# snc98_Display_15x7-Seg_3-digit_LTD040.net
KiCad netlist of a schematic drawn in EAGLE
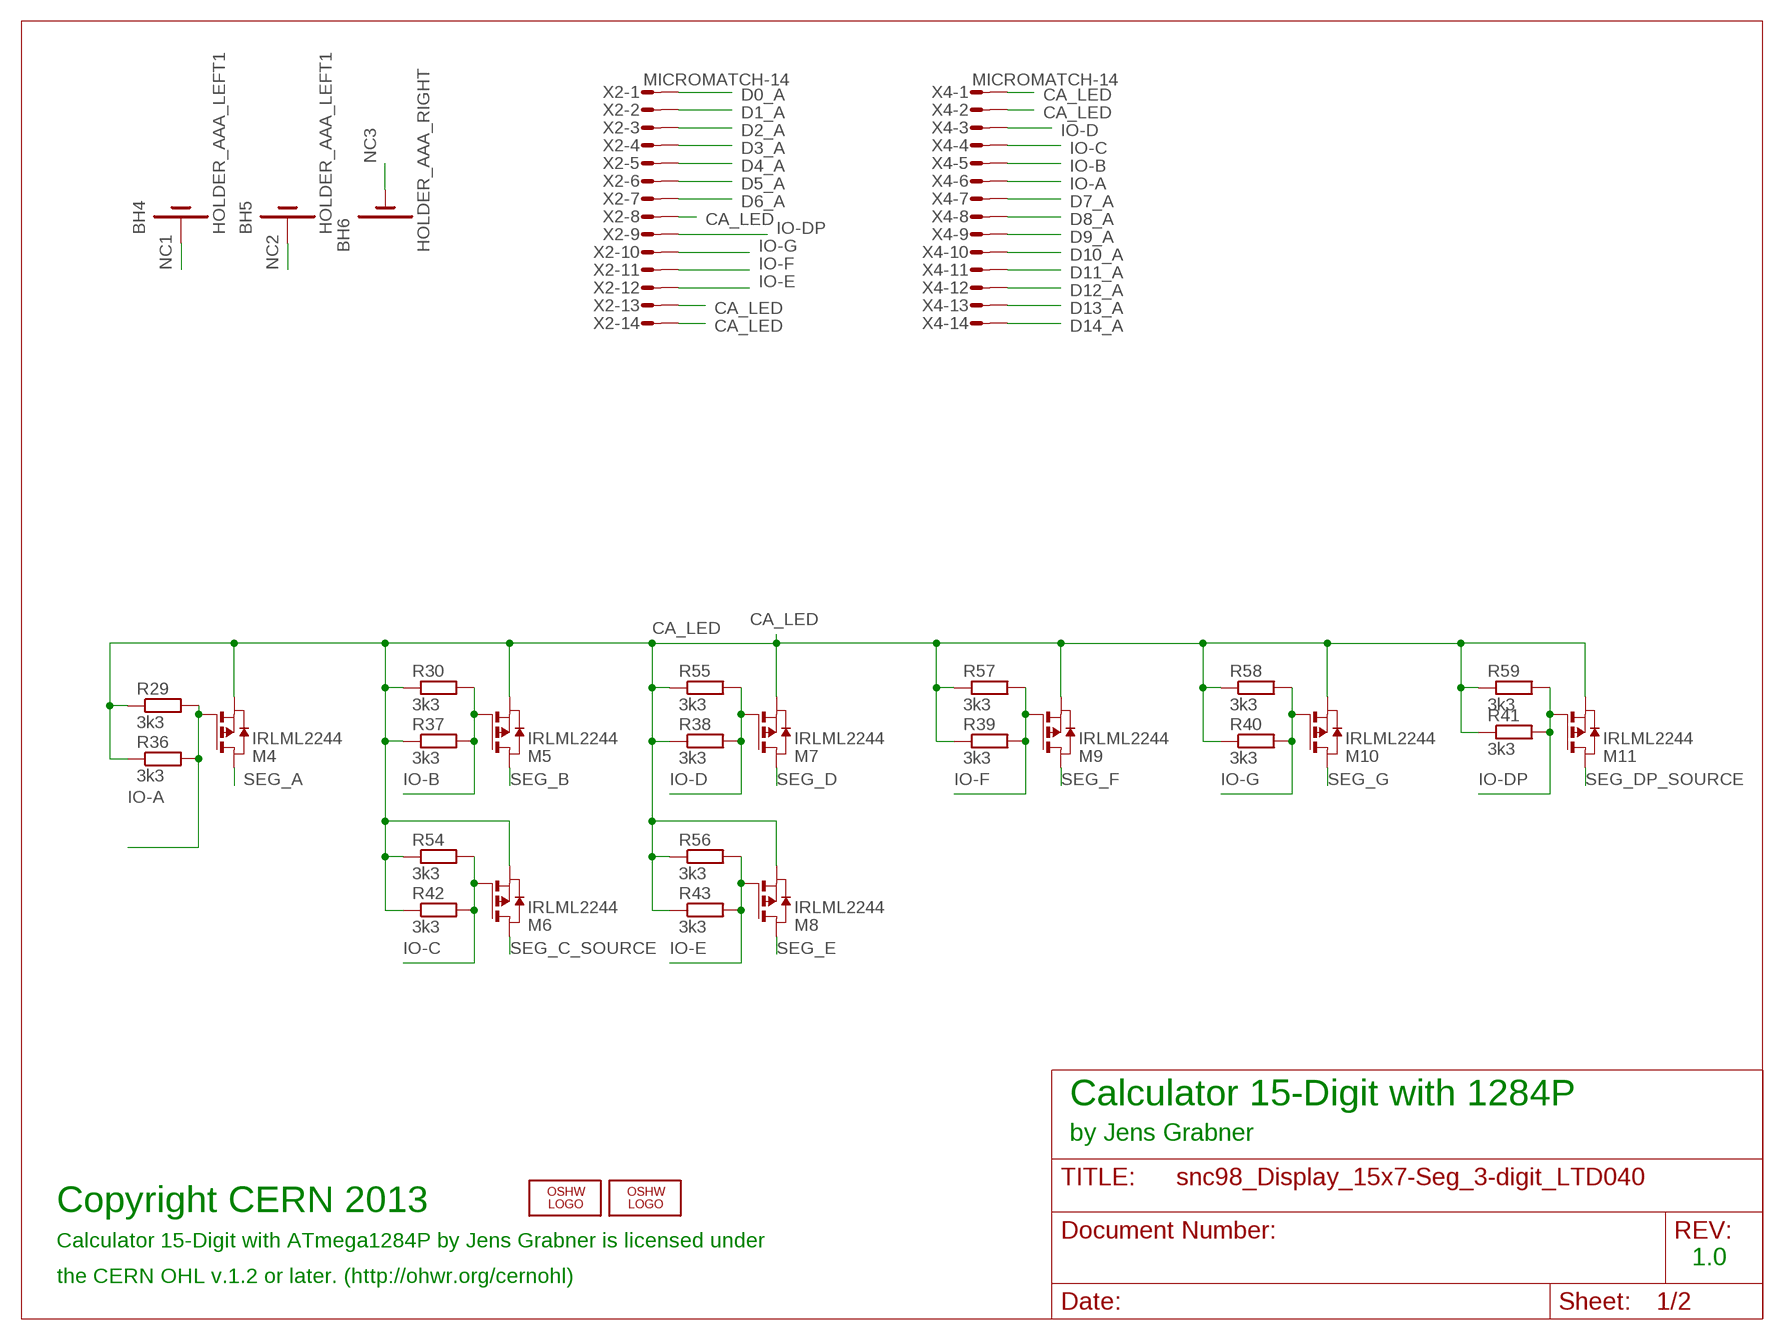
[diagram p0: schematic, sheet 1]
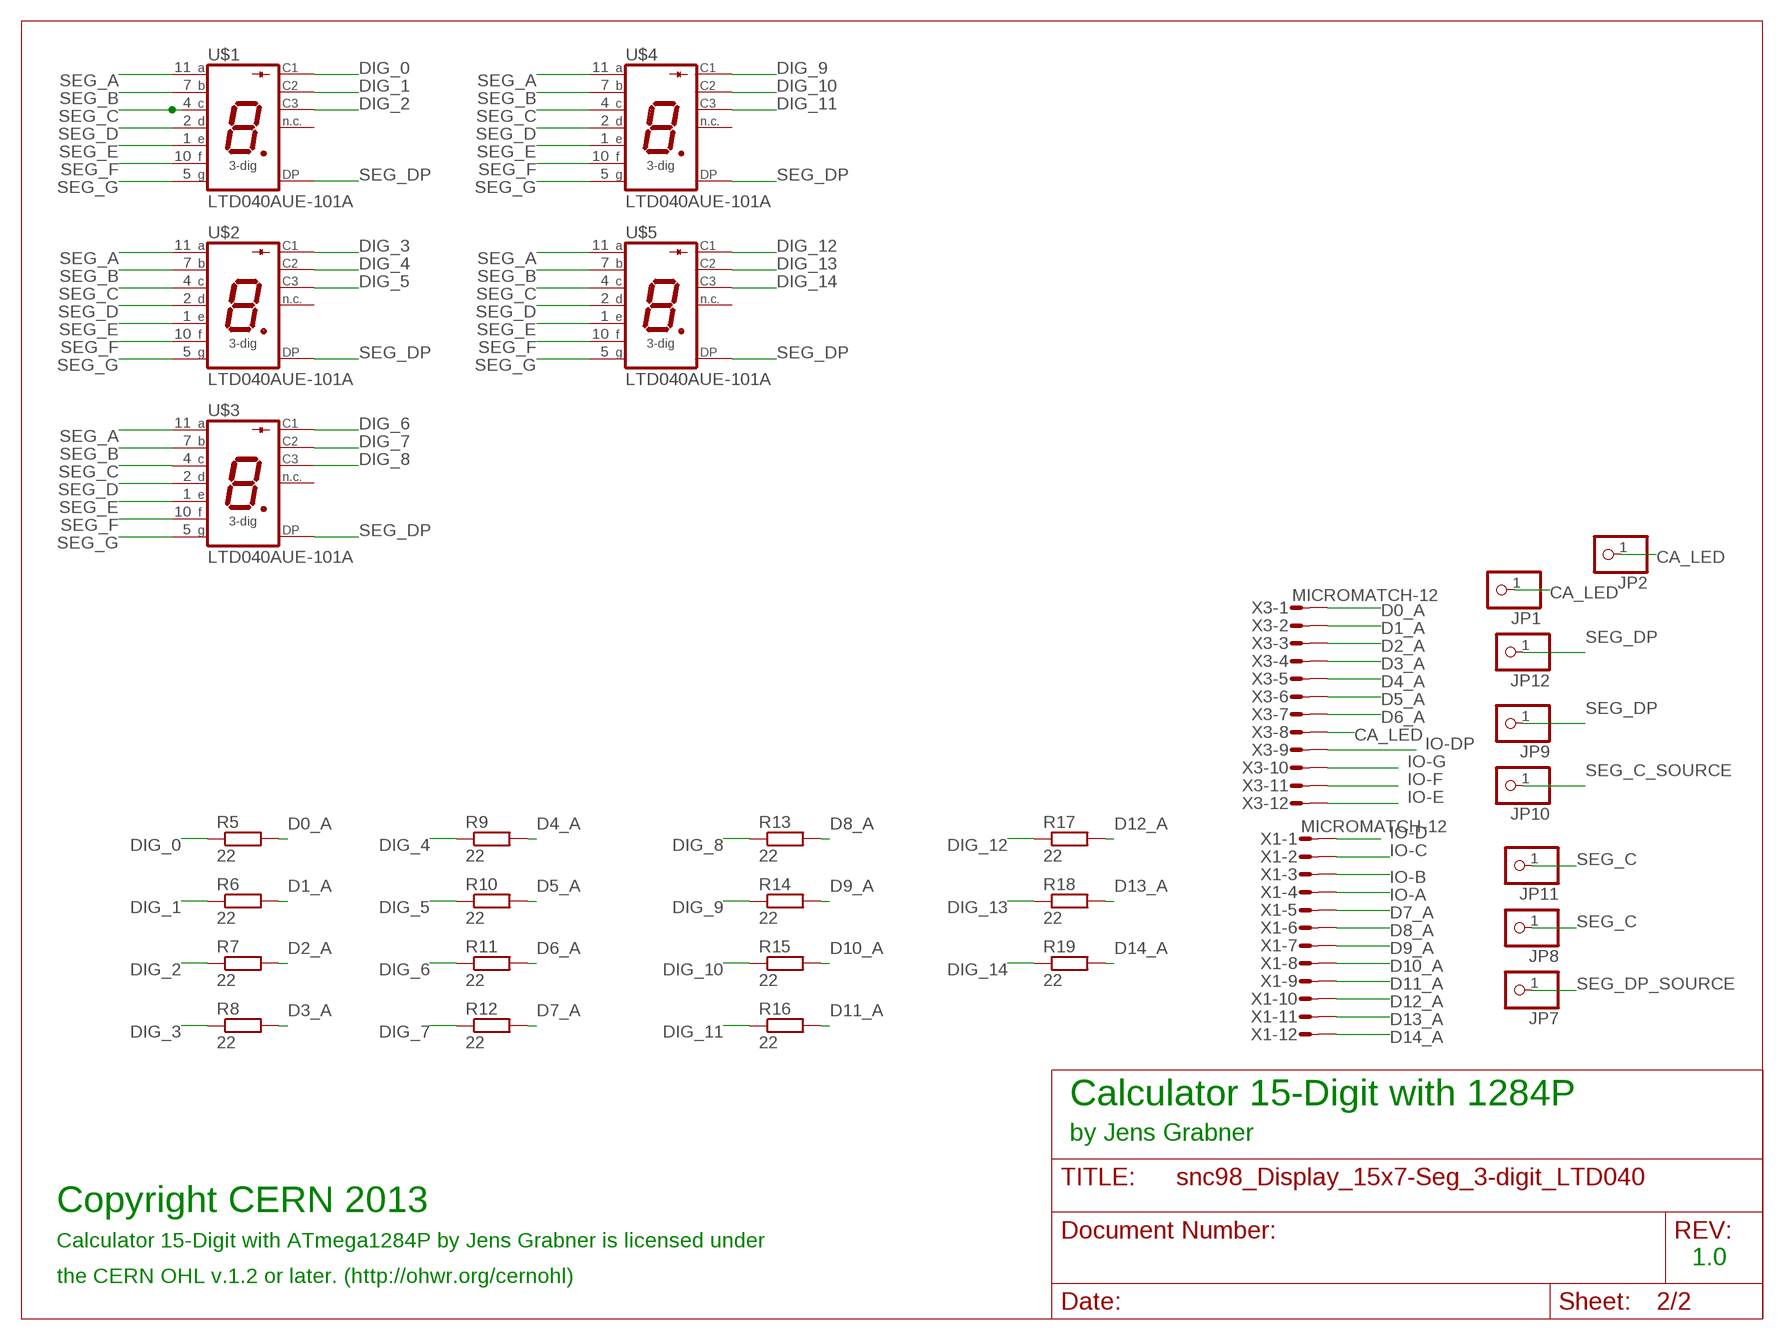
[diagram p1: schematic, sheet 2]

(export (version "E")
  (design (tool "Eeschema 10.0.6"))
  (components
    (comp (ref "BH4")
      (value "HOLDER_AAA_LEFT1")
      (footprint "eagle-import:BATTERY-AAA-LEFT")
      (libsource (lib "eagle-import") (part "HOLDER_AAA_LEFT1"))
    )
    (comp (ref "BH5")
      (value "HOLDER_AAA_LEFT1")
      (footprint "eagle-import:BATTERY-AAA-LEFT")
      (libsource (lib "eagle-import") (part "HOLDER_AAA_LEFT1"))
    )
    (comp (ref "BH6")
      (value "HOLDER_AAA_RIGHT")
      (footprint "eagle-import:BATTERY-AAA-RIGHT")
      (libsource (lib "eagle-import") (part "HOLDER_AAA_RIGHT"))
    )
    (comp (ref "LOGO1")
      (value "OSHW_LOGO_8MILX0150-NT")
      (footprint "eagle-import:OSHW_8X150_NOTEXT")
      (libsource (lib "eagle-import") (part "OSHW_LOGO_8MILX0150-NT"))
    )
    (comp (ref "LOGO3")
      (value "OSHW_LOGO_6MILX0100-NT")
      (footprint "eagle-import:OSHW_6X100_NOTEXT")
      (libsource (lib "eagle-import") (part "OSHW_LOGO_6MILX0100-NT"))
    )
    (comp (ref "M4")
      (value "IRLML2244")
      (footprint "eagle-import:SOT-23")
      (libsource (lib "eagle-import") (part "IRLML6402"))
    )
    (comp (ref "M5")
      (value "IRLML2244")
      (footprint "eagle-import:SOT-23")
      (libsource (lib "eagle-import") (part "IRLML6402"))
    )
    (comp (ref "M6")
      (value "IRLML2244")
      (footprint "eagle-import:SOT-23")
      (libsource (lib "eagle-import") (part "IRLML6402"))
    )
    (comp (ref "M7")
      (value "IRLML2244")
      (footprint "eagle-import:SOT-23")
      (libsource (lib "eagle-import") (part "IRLML6402"))
    )
    (comp (ref "M8")
      (value "IRLML2244")
      (footprint "eagle-import:SOT-23")
      (libsource (lib "eagle-import") (part "IRLML6402"))
    )
    (comp (ref "M9")
      (value "IRLML2244")
      (footprint "eagle-import:SOT-23")
      (libsource (lib "eagle-import") (part "IRLML6402"))
    )
    (comp (ref "M10")
      (value "IRLML2244")
      (footprint "eagle-import:SOT-23")
      (libsource (lib "eagle-import") (part "IRLML6402"))
    )
    (comp (ref "M11")
      (value "IRLML2244")
      (footprint "eagle-import:SOT-23")
      (libsource (lib "eagle-import") (part "IRLML6402"))
    )
    (comp (ref "R29")
      (value "3k3")
      (footprint "eagle-import:0204_5")
      (libsource (lib "eagle-import") (part "R-EU_0204/5"))
    )
    (comp (ref "R30")
      (value "3k3")
      (footprint "eagle-import:0204_5")
      (libsource (lib "eagle-import") (part "R-EU_0204/5"))
    )
    (comp (ref "R36")
      (value "3k3")
      (footprint "eagle-import:R1206")
      (libsource (lib "eagle-import") (part "R-EU_R1206"))
    )
    (comp (ref "R37")
      (value "3k3")
      (footprint "eagle-import:R1206")
      (libsource (lib "eagle-import") (part "R-EU_R1206"))
    )
    (comp (ref "R38")
      (value "3k3")
      (footprint "eagle-import:R1206")
      (libsource (lib "eagle-import") (part "R-EU_R1206"))
    )
    (comp (ref "R39")
      (value "3k3")
      (footprint "eagle-import:R1206")
      (libsource (lib "eagle-import") (part "R-EU_R1206"))
    )
    (comp (ref "R40")
      (value "3k3")
      (footprint "eagle-import:R1206")
      (libsource (lib "eagle-import") (part "R-EU_R1206"))
    )
    (comp (ref "R41")
      (value "3k3")
      (footprint "eagle-import:R1206")
      (libsource (lib "eagle-import") (part "R-EU_R1206"))
    )
    (comp (ref "R42")
      (value "3k3")
      (footprint "eagle-import:R1206")
      (libsource (lib "eagle-import") (part "R-EU_R1206"))
    )
    (comp (ref "R43")
      (value "3k3")
      (footprint "eagle-import:R1206")
      (libsource (lib "eagle-import") (part "R-EU_R1206"))
    )
    (comp (ref "R54")
      (value "3k3")
      (footprint "eagle-import:0204_5")
      (libsource (lib "eagle-import") (part "R-EU_0204/5"))
    )
    (comp (ref "R55")
      (value "3k3")
      (footprint "eagle-import:0204_5")
      (libsource (lib "eagle-import") (part "R-EU_0204/5"))
    )
    (comp (ref "R56")
      (value "3k3")
      (footprint "eagle-import:0204_5")
      (libsource (lib "eagle-import") (part "R-EU_0204/5"))
    )
    (comp (ref "R57")
      (value "3k3")
      (footprint "eagle-import:0204_5")
      (libsource (lib "eagle-import") (part "R-EU_0204/5"))
    )
    (comp (ref "R58")
      (value "3k3")
      (footprint "eagle-import:0204_5")
      (libsource (lib "eagle-import") (part "R-EU_0204/5"))
    )
    (comp (ref "R59")
      (value "3k3")
      (footprint "eagle-import:0204_5")
      (libsource (lib "eagle-import") (part "R-EU_0204/5"))
    )
    (comp (ref "X2")
      (value "MICROMATCH-14")
      (footprint "eagle-import:MICROMATCH-14")
      (fields (field (name "MF") "FARNELL") (field (name "MPN") "8-215464-4"))
      (libsource (lib "eagle-import") (part "MICROMATCH-14"))
    )
    (comp (ref "X4")
      (value "MICROMATCH-14")
      (footprint "eagle-import:MICROMATCH-14")
      (fields (field (name "MF") "FARNELL") (field (name "MPN") "8-215464-4"))
      (libsource (lib "eagle-import") (part "MICROMATCH-14"))
    )
    (comp (ref "JP1")
      (value "PINHD-1X1")
      (footprint "eagle-import:1X01")
      (libsource (lib "eagle-import") (part "PINHD-1X1"))
    )
    (comp (ref "JP2")
      (value "PINHD-1X1")
      (footprint "eagle-import:1X01")
      (libsource (lib "eagle-import") (part "PINHD-1X1"))
    )
    (comp (ref "JP7")
      (value "PINHD-1X1")
      (footprint "eagle-import:1X01")
      (libsource (lib "eagle-import") (part "PINHD-1X1"))
    )
    (comp (ref "JP8")
      (value "PINHD-1X1")
      (footprint "eagle-import:1X01")
      (libsource (lib "eagle-import") (part "PINHD-1X1"))
    )
    (comp (ref "JP9")
      (value "PINHD-1X1")
      (footprint "eagle-import:1X01")
      (libsource (lib "eagle-import") (part "PINHD-1X1"))
    )
    (comp (ref "JP10")
      (value "PINHD-1X1")
      (footprint "eagle-import:1X01")
      (libsource (lib "eagle-import") (part "PINHD-1X1"))
    )
    (comp (ref "JP11")
      (value "PINHD-1X1")
      (footprint "eagle-import:1X01")
      (libsource (lib "eagle-import") (part "PINHD-1X1"))
    )
    (comp (ref "JP12")
      (value "PINHD-1X1")
      (footprint "eagle-import:1X01")
      (libsource (lib "eagle-import") (part "PINHD-1X1"))
    )
    (comp (ref "R5")
      (value "22")
      (footprint "eagle-import:R1210")
      (libsource (lib "eagle-import") (part "R-EU_R1210"))
    )
    (comp (ref "R6")
      (value "22")
      (footprint "eagle-import:R1210")
      (libsource (lib "eagle-import") (part "R-EU_R1210"))
    )
    (comp (ref "R7")
      (value "22")
      (footprint "eagle-import:R1210")
      (libsource (lib "eagle-import") (part "R-EU_R1210"))
    )
    (comp (ref "R8")
      (value "22")
      (footprint "eagle-import:R1210")
      (libsource (lib "eagle-import") (part "R-EU_R1210"))
    )
    (comp (ref "R9")
      (value "22")
      (footprint "eagle-import:R1210")
      (libsource (lib "eagle-import") (part "R-EU_R1210"))
    )
    (comp (ref "R10")
      (value "22")
      (footprint "eagle-import:R1210")
      (libsource (lib "eagle-import") (part "R-EU_R1210"))
    )
    (comp (ref "R11")
      (value "22")
      (footprint "eagle-import:R1210")
      (libsource (lib "eagle-import") (part "R-EU_R1210"))
    )
    (comp (ref "R12")
      (value "22")
      (footprint "eagle-import:R1210")
      (libsource (lib "eagle-import") (part "R-EU_R1210"))
    )
    (comp (ref "R13")
      (value "22")
      (footprint "eagle-import:R1210")
      (libsource (lib "eagle-import") (part "R-EU_R1210"))
    )
    (comp (ref "R14")
      (value "22")
      (footprint "eagle-import:R1210")
      (libsource (lib "eagle-import") (part "R-EU_R1210"))
    )
    (comp (ref "R15")
      (value "22")
      (footprint "eagle-import:R1210")
      (libsource (lib "eagle-import") (part "R-EU_R1210"))
    )
    (comp (ref "R16")
      (value "22")
      (footprint "eagle-import:R1210")
      (libsource (lib "eagle-import") (part "R-EU_R1210"))
    )
    (comp (ref "R17")
      (value "22")
      (footprint "eagle-import:R1210")
      (libsource (lib "eagle-import") (part "R-EU_R1210"))
    )
    (comp (ref "R18")
      (value "22")
      (footprint "eagle-import:R1210")
      (libsource (lib "eagle-import") (part "R-EU_R1210"))
    )
    (comp (ref "R19")
      (value "22")
      (footprint "eagle-import:R1210")
      (libsource (lib "eagle-import") (part "R-EU_R1210"))
    )
    (comp (ref "U$1")
      (value "LTD040AUE-101A")
      (footprint "eagle-import:LTD040AUE-101A")
      (libsource (lib "eagle-import") (part "LTD040AUE-101A"))
    )
    (comp (ref "U$2")
      (value "LTD040AUE-101A")
      (footprint "eagle-import:LTD040AUE-101A")
      (libsource (lib "eagle-import") (part "LTD040AUE-101A"))
    )
    (comp (ref "U$3")
      (value "LTD040AUE-101A")
      (footprint "eagle-import:LTD040AUE-101A")
      (libsource (lib "eagle-import") (part "LTD040AUE-101A"))
    )
    (comp (ref "U$4")
      (value "LTD040AUE-101A")
      (footprint "eagle-import:LTD040AUE-101A")
      (libsource (lib "eagle-import") (part "LTD040AUE-101A"))
    )
    (comp (ref "U$5")
      (value "LTD040AUE-101A")
      (footprint "eagle-import:LTD040AUE-101A")
      (libsource (lib "eagle-import") (part "LTD040AUE-101A"))
    )
    (comp (ref "X1")
      (value "MICROMATCH-12")
      (footprint "eagle-import:MICROMATCH-12")
      (fields (field (name "MF") "FARNELL") (field (name "MPN") "8-215464-2"))
      (libsource (lib "eagle-import") (part "MICROMATCH-12"))
    )
    (comp (ref "X3")
      (value "MICROMATCH-12")
      (footprint "eagle-import:MICROMATCH-12")
      (fields (field (name "MF") "FARNELL") (field (name "MPN") "8-215464-2"))
      (libsource (lib "eagle-import") (part "MICROMATCH-12"))
    )
  )
  (nets
    (net (code "1") (name "CA_LED") (class "Default")
      (node (ref "JP1") (pin "1") (pinfunction "1_1") (pintype "passive"))
      (node (ref "JP2") (pin "1") (pinfunction "1_1") (pintype "passive"))
      (node (ref "M10") (pin "2") (pinfunction "S_2") (pintype "passive"))
      (node (ref "M11") (pin "2") (pinfunction "S_2") (pintype "passive"))
      (node (ref "M4") (pin "2") (pinfunction "S_2") (pintype "passive"))
      (node (ref "M5") (pin "2") (pinfunction "S_2") (pintype "passive"))
      (node (ref "M6") (pin "2") (pinfunction "S_2") (pintype "passive"))
      (node (ref "M7") (pin "2") (pinfunction "S_2") (pintype "passive"))
      (node (ref "M8") (pin "2") (pinfunction "S_2") (pintype "passive"))
      (node (ref "M9") (pin "2") (pinfunction "S_2") (pintype "passive"))
      (node (ref "R29") (pin "1") (pinfunction "1_1") (pintype "passive"))
      (node (ref "R30") (pin "1") (pinfunction "1_1") (pintype "passive"))
      (node (ref "R36") (pin "1") (pinfunction "1_1") (pintype "passive"))
      (node (ref "R37") (pin "1") (pinfunction "1_1") (pintype "passive"))
      (node (ref "R38") (pin "1") (pinfunction "1_1") (pintype "passive"))
      (node (ref "R39") (pin "1") (pinfunction "1_1") (pintype "passive"))
      (node (ref "R40") (pin "1") (pinfunction "1_1") (pintype "passive"))
      (node (ref "R41") (pin "1") (pinfunction "1_1") (pintype "passive"))
      (node (ref "R42") (pin "1") (pinfunction "1_1") (pintype "passive"))
      (node (ref "R43") (pin "1") (pinfunction "1_1") (pintype "passive"))
      (node (ref "R54") (pin "1") (pinfunction "1_1") (pintype "passive"))
      (node (ref "R55") (pin "1") (pinfunction "1_1") (pintype "passive"))
      (node (ref "R56") (pin "1") (pinfunction "1_1") (pintype "passive"))
      (node (ref "R57") (pin "1") (pinfunction "1_1") (pintype "passive"))
      (node (ref "R58") (pin "1") (pinfunction "1_1") (pintype "passive"))
      (node (ref "R59") (pin "1") (pinfunction "1_1") (pintype "passive"))
      (node (ref "X2") (pin "13") (pinfunction "S_13") (pintype "passive"))
      (node (ref "X2") (pin "14") (pinfunction "S_14") (pintype "passive"))
      (node (ref "X2") (pin "8") (pinfunction "S_8") (pintype "passive"))
      (node (ref "X3") (pin "8") (pinfunction "S_8") (pintype "passive"))
      (node (ref "X4") (pin "1") (pinfunction "S_1") (pintype "passive"))
      (node (ref "X4") (pin "2") (pinfunction "S_2") (pintype "passive"))
    )
    (net (code "2") (name "D0_A") (class "Default")
      (node (ref "R5") (pin "2") (pinfunction "2_2") (pintype "passive"))
      (node (ref "X2") (pin "1") (pinfunction "S_1") (pintype "passive"))
      (node (ref "X3") (pin "1") (pinfunction "S_1") (pintype "passive"))
    )
    (net (code "3") (name "D1_A") (class "Default")
      (node (ref "R6") (pin "2") (pinfunction "2_2") (pintype "passive"))
      (node (ref "X2") (pin "2") (pinfunction "S_2") (pintype "passive"))
      (node (ref "X3") (pin "2") (pinfunction "S_2") (pintype "passive"))
    )
    (net (code "4") (name "D2_A") (class "Default")
      (node (ref "R7") (pin "2") (pinfunction "2_2") (pintype "passive"))
      (node (ref "X2") (pin "3") (pinfunction "S_3") (pintype "passive"))
      (node (ref "X3") (pin "3") (pinfunction "S_3") (pintype "passive"))
    )
    (net (code "5") (name "D3_A") (class "Default")
      (node (ref "R8") (pin "2") (pinfunction "2_2") (pintype "passive"))
      (node (ref "X2") (pin "4") (pinfunction "S_4") (pintype "passive"))
      (node (ref "X3") (pin "4") (pinfunction "S_4") (pintype "passive"))
    )
    (net (code "6") (name "D4_A") (class "Default")
      (node (ref "R9") (pin "2") (pinfunction "2_2") (pintype "passive"))
      (node (ref "X2") (pin "5") (pinfunction "S_5") (pintype "passive"))
      (node (ref "X3") (pin "5") (pinfunction "S_5") (pintype "passive"))
    )
    (net (code "7") (name "D5_A") (class "Default")
      (node (ref "R10") (pin "2") (pinfunction "2_2") (pintype "passive"))
      (node (ref "X2") (pin "6") (pinfunction "S_6") (pintype "passive"))
      (node (ref "X3") (pin "6") (pinfunction "S_6") (pintype "passive"))
    )
    (net (code "8") (name "D6_A") (class "Default")
      (node (ref "R11") (pin "2") (pinfunction "2_2") (pintype "passive"))
      (node (ref "X2") (pin "7") (pinfunction "S_7") (pintype "passive"))
      (node (ref "X3") (pin "7") (pinfunction "S_7") (pintype "passive"))
    )
    (net (code "9") (name "D7_A") (class "Default")
      (node (ref "R12") (pin "2") (pinfunction "2_2") (pintype "passive"))
      (node (ref "X1") (pin "5") (pinfunction "S_5") (pintype "passive"))
      (node (ref "X4") (pin "7") (pinfunction "S_7") (pintype "passive"))
    )
    (net (code "10") (name "D8_A") (class "Default")
      (node (ref "R13") (pin "2") (pinfunction "2_2") (pintype "passive"))
      (node (ref "X1") (pin "6") (pinfunction "S_6") (pintype "passive"))
      (node (ref "X4") (pin "8") (pinfunction "S_8") (pintype "passive"))
    )
    (net (code "11") (name "D9_A") (class "Default")
      (node (ref "R14") (pin "2") (pinfunction "2_2") (pintype "passive"))
      (node (ref "X1") (pin "7") (pinfunction "S_7") (pintype "passive"))
      (node (ref "X4") (pin "9") (pinfunction "S_9") (pintype "passive"))
    )
    (net (code "12") (name "D10_A") (class "Default")
      (node (ref "R15") (pin "2") (pinfunction "2_2") (pintype "passive"))
      (node (ref "X1") (pin "8") (pinfunction "S_8") (pintype "passive"))
      (node (ref "X4") (pin "10") (pinfunction "S_10") (pintype "passive"))
    )
    (net (code "13") (name "D11_A") (class "Default")
      (node (ref "R16") (pin "2") (pinfunction "2_2") (pintype "passive"))
      (node (ref "X1") (pin "9") (pinfunction "S_9") (pintype "passive"))
      (node (ref "X4") (pin "11") (pinfunction "S_11") (pintype "passive"))
    )
    (net (code "14") (name "D12_A") (class "Default")
      (node (ref "R17") (pin "2") (pinfunction "2_2") (pintype "passive"))
      (node (ref "X1") (pin "10") (pinfunction "S_10") (pintype "passive"))
      (node (ref "X4") (pin "12") (pinfunction "S_12") (pintype "passive"))
    )
    (net (code "15") (name "D13_A") (class "Default")
      (node (ref "R18") (pin "2") (pinfunction "2_2") (pintype "passive"))
      (node (ref "X1") (pin "11") (pinfunction "S_11") (pintype "passive"))
      (node (ref "X4") (pin "13") (pinfunction "S_13") (pintype "passive"))
    )
    (net (code "16") (name "D14_A") (class "Default")
      (node (ref "R19") (pin "2") (pinfunction "2_2") (pintype "passive"))
      (node (ref "X1") (pin "12") (pinfunction "S_12") (pintype "passive"))
      (node (ref "X4") (pin "14") (pinfunction "S_14") (pintype "passive"))
    )
    (net (code "17") (name "DIG_0") (class "Default")
      (node (ref "R5") (pin "1") (pinfunction "1_1") (pintype "passive"))
      (node (ref "U$1") (pin "12") (pinfunction "C1_12") (pintype "passive"))
    )
    (net (code "18") (name "DIG_1") (class "Default")
      (node (ref "R6") (pin "1") (pinfunction "1_1") (pintype "passive"))
      (node (ref "U$1") (pin "9") (pinfunction "C2_9") (pintype "passive"))
    )
    (net (code "19") (name "DIG_2") (class "Default")
      (node (ref "R7") (pin "1") (pinfunction "1_1") (pintype "passive"))
      (node (ref "U$1") (pin "8") (pinfunction "C3_8") (pintype "passive"))
    )
    (net (code "20") (name "DIG_3") (class "Default")
      (node (ref "R8") (pin "1") (pinfunction "1_1") (pintype "passive"))
      (node (ref "U$2") (pin "12") (pinfunction "C1_12") (pintype "passive"))
    )
    (net (code "21") (name "DIG_4") (class "Default")
      (node (ref "R9") (pin "1") (pinfunction "1_1") (pintype "passive"))
      (node (ref "U$2") (pin "9") (pinfunction "C2_9") (pintype "passive"))
    )
    (net (code "22") (name "DIG_5") (class "Default")
      (node (ref "R10") (pin "1") (pinfunction "1_1") (pintype "passive"))
      (node (ref "U$2") (pin "8") (pinfunction "C3_8") (pintype "passive"))
    )
    (net (code "23") (name "DIG_6") (class "Default")
      (node (ref "R11") (pin "1") (pinfunction "1_1") (pintype "passive"))
      (node (ref "U$3") (pin "12") (pinfunction "C1_12") (pintype "passive"))
    )
    (net (code "24") (name "DIG_7") (class "Default")
      (node (ref "R12") (pin "1") (pinfunction "1_1") (pintype "passive"))
      (node (ref "U$3") (pin "9") (pinfunction "C2_9") (pintype "passive"))
    )
    (net (code "25") (name "DIG_8") (class "Default")
      (node (ref "R13") (pin "1") (pinfunction "1_1") (pintype "passive"))
      (node (ref "U$3") (pin "8") (pinfunction "C3_8") (pintype "passive"))
    )
    (net (code "26") (name "DIG_9") (class "Default")
      (node (ref "R14") (pin "1") (pinfunction "1_1") (pintype "passive"))
      (node (ref "U$4") (pin "12") (pinfunction "C1_12") (pintype "passive"))
    )
    (net (code "27") (name "DIG_10") (class "Default")
      (node (ref "R15") (pin "1") (pinfunction "1_1") (pintype "passive"))
      (node (ref "U$4") (pin "9") (pinfunction "C2_9") (pintype "passive"))
    )
    (net (code "28") (name "DIG_11") (class "Default")
      (node (ref "R16") (pin "1") (pinfunction "1_1") (pintype "passive"))
      (node (ref "U$4") (pin "8") (pinfunction "C3_8") (pintype "passive"))
    )
    (net (code "29") (name "DIG_12") (class "Default")
      (node (ref "R17") (pin "1") (pinfunction "1_1") (pintype "passive"))
      (node (ref "U$5") (pin "12") (pinfunction "C1_12") (pintype "passive"))
    )
    (net (code "30") (name "DIG_13") (class "Default")
      (node (ref "R18") (pin "1") (pinfunction "1_1") (pintype "passive"))
      (node (ref "U$5") (pin "9") (pinfunction "C2_9") (pintype "passive"))
    )
    (net (code "31") (name "DIG_14") (class "Default")
      (node (ref "R19") (pin "1") (pinfunction "1_1") (pintype "passive"))
      (node (ref "U$5") (pin "8") (pinfunction "C3_8") (pintype "passive"))
    )
    (net (code "32") (name "IO-A") (class "Default")
      (node (ref "M4") (pin "1") (pinfunction "G_1") (pintype "passive"))
      (node (ref "R29") (pin "2") (pinfunction "2_2") (pintype "passive"))
      (node (ref "R36") (pin "2") (pinfunction "2_2") (pintype "passive"))
      (node (ref "X1") (pin "4") (pinfunction "S_4") (pintype "passive"))
      (node (ref "X4") (pin "6") (pinfunction "S_6") (pintype "passive"))
    )
    (net (code "33") (name "IO-B") (class "Default")
      (node (ref "M5") (pin "1") (pinfunction "G_1") (pintype "passive"))
      (node (ref "R30") (pin "2") (pinfunction "2_2") (pintype "passive"))
      (node (ref "R37") (pin "2") (pinfunction "2_2") (pintype "passive"))
      (node (ref "X1") (pin "3") (pinfunction "S_3") (pintype "passive"))
      (node (ref "X4") (pin "5") (pinfunction "S_5") (pintype "passive"))
    )
    (net (code "34") (name "IO-C") (class "Default")
      (node (ref "M6") (pin "1") (pinfunction "G_1") (pintype "passive"))
      (node (ref "R42") (pin "2") (pinfunction "2_2") (pintype "passive"))
      (node (ref "R54") (pin "2") (pinfunction "2_2") (pintype "passive"))
      (node (ref "X1") (pin "2") (pinfunction "S_2") (pintype "passive"))
      (node (ref "X4") (pin "4") (pinfunction "S_4") (pintype "passive"))
    )
    (net (code "35") (name "IO-D") (class "Default")
      (node (ref "M7") (pin "1") (pinfunction "G_1") (pintype "passive"))
      (node (ref "R38") (pin "2") (pinfunction "2_2") (pintype "passive"))
      (node (ref "R55") (pin "2") (pinfunction "2_2") (pintype "passive"))
      (node (ref "X1") (pin "1") (pinfunction "S_1") (pintype "passive"))
      (node (ref "X4") (pin "3") (pinfunction "S_3") (pintype "passive"))
    )
    (net (code "36") (name "IO-DP") (class "Default")
      (node (ref "M11") (pin "1") (pinfunction "G_1") (pintype "passive"))
      (node (ref "R41") (pin "2") (pinfunction "2_2") (pintype "passive"))
      (node (ref "R59") (pin "2") (pinfunction "2_2") (pintype "passive"))
      (node (ref "X2") (pin "9") (pinfunction "S_9") (pintype "passive"))
      (node (ref "X3") (pin "9") (pinfunction "S_9") (pintype "passive"))
    )
    (net (code "37") (name "IO-E") (class "Default")
      (node (ref "M8") (pin "1") (pinfunction "G_1") (pintype "passive"))
      (node (ref "R43") (pin "2") (pinfunction "2_2") (pintype "passive"))
      (node (ref "R56") (pin "2") (pinfunction "2_2") (pintype "passive"))
      (node (ref "X2") (pin "12") (pinfunction "S_12") (pintype "passive"))
      (node (ref "X3") (pin "12") (pinfunction "S_12") (pintype "passive"))
    )
    (net (code "38") (name "IO-F") (class "Default")
      (node (ref "M9") (pin "1") (pinfunction "G_1") (pintype "passive"))
      (node (ref "R39") (pin "2") (pinfunction "2_2") (pintype "passive"))
      (node (ref "R57") (pin "2") (pinfunction "2_2") (pintype "passive"))
      (node (ref "X2") (pin "11") (pinfunction "S_11") (pintype "passive"))
      (node (ref "X3") (pin "11") (pinfunction "S_11") (pintype "passive"))
    )
    (net (code "39") (name "IO-G") (class "Default")
      (node (ref "M10") (pin "1") (pinfunction "G_1") (pintype "passive"))
      (node (ref "R40") (pin "2") (pinfunction "2_2") (pintype "passive"))
      (node (ref "R58") (pin "2") (pinfunction "2_2") (pintype "passive"))
      (node (ref "X2") (pin "10") (pinfunction "S_10") (pintype "passive"))
      (node (ref "X3") (pin "10") (pinfunction "S_10") (pintype "passive"))
    )
    (net (code "40") (name "NC1") (class "Default")
      (node (ref "BH4") (pin "P1") (pinfunction "+_P1") (pintype "power_in"))
      (node (ref "BH4") (pin "P2") (pinfunction "+_P2") (pintype "power_in"))
      (node (ref "BH4") (pin "P3") (pinfunction "+_P3") (pintype "power_in"))
      (node (ref "BH4") (pin "P4") (pinfunction "+_P4") (pintype "power_in"))
    )
    (net (code "41") (name "NC2") (class "Default")
      (node (ref "BH5") (pin "P1") (pinfunction "+_P1") (pintype "power_in"))
      (node (ref "BH5") (pin "P2") (pinfunction "+_P2") (pintype "power_in"))
      (node (ref "BH5") (pin "P3") (pinfunction "+_P3") (pintype "power_in"))
      (node (ref "BH5") (pin "P4") (pinfunction "+_P4") (pintype "power_in"))
    )
    (net (code "42") (name "NC3") (class "Default")
      (node (ref "BH6") (pin "M1") (pinfunction "-_M1") (pintype "power_in"))
      (node (ref "BH6") (pin "M2") (pinfunction "-_M2") (pintype "power_in"))
      (node (ref "BH6") (pin "M3") (pinfunction "-_M3") (pintype "power_in"))
      (node (ref "BH6") (pin "M4") (pinfunction "-_M4") (pintype "power_in"))
    )
    (net (code "43") (name "SEG_A") (class "Default")
      (node (ref "M4") (pin "3") (pinfunction "D_3") (pintype "passive"))
      (node (ref "U$1") (pin "11") (pinfunction "A_11") (pintype "passive"))
      (node (ref "U$2") (pin "11") (pinfunction "A_11") (pintype "passive"))
      (node (ref "U$3") (pin "11") (pinfunction "A_11") (pintype "passive"))
      (node (ref "U$4") (pin "11") (pinfunction "A_11") (pintype "passive"))
      (node (ref "U$5") (pin "11") (pinfunction "A_11") (pintype "passive"))
    )
    (net (code "44") (name "SEG_B") (class "Default")
      (node (ref "M5") (pin "3") (pinfunction "D_3") (pintype "passive"))
      (node (ref "U$1") (pin "7") (pinfunction "B_7") (pintype "passive"))
      (node (ref "U$2") (pin "7") (pinfunction "B_7") (pintype "passive"))
      (node (ref "U$3") (pin "7") (pinfunction "B_7") (pintype "passive"))
      (node (ref "U$4") (pin "7") (pinfunction "B_7") (pintype "passive"))
      (node (ref "U$5") (pin "7") (pinfunction "B_7") (pintype "passive"))
    )
    (net (code "45") (name "SEG_C") (class "Default")
      (node (ref "JP11") (pin "1") (pinfunction "1_1") (pintype "passive"))
      (node (ref "JP8") (pin "1") (pinfunction "1_1") (pintype "passive"))
      (node (ref "U$1") (pin "4") (pinfunction "C_4") (pintype "passive"))
      (node (ref "U$2") (pin "4") (pinfunction "C_4") (pintype "passive"))
      (node (ref "U$3") (pin "4") (pinfunction "C_4") (pintype "passive"))
      (node (ref "U$4") (pin "4") (pinfunction "C_4") (pintype "passive"))
      (node (ref "U$5") (pin "4") (pinfunction "C_4") (pintype "passive"))
    )
    (net (code "46") (name "SEG_C_SOURCE") (class "Default")
      (node (ref "JP10") (pin "1") (pinfunction "1_1") (pintype "passive"))
      (node (ref "M6") (pin "3") (pinfunction "D_3") (pintype "passive"))
    )
    (net (code "47") (name "SEG_D") (class "Default")
      (node (ref "M7") (pin "3") (pinfunction "D_3") (pintype "passive"))
      (node (ref "U$1") (pin "2") (pinfunction "D_2") (pintype "passive"))
      (node (ref "U$2") (pin "2") (pinfunction "D_2") (pintype "passive"))
      (node (ref "U$3") (pin "2") (pinfunction "D_2") (pintype "passive"))
      (node (ref "U$4") (pin "2") (pinfunction "D_2") (pintype "passive"))
      (node (ref "U$5") (pin "2") (pinfunction "D_2") (pintype "passive"))
    )
    (net (code "48") (name "SEG_DP") (class "Default")
      (node (ref "JP12") (pin "1") (pinfunction "1_1") (pintype "passive"))
      (node (ref "JP9") (pin "1") (pinfunction "1_1") (pintype "passive"))
      (node (ref "U$1") (pin "3") (pinfunction "DP_3") (pintype "passive"))
      (node (ref "U$2") (pin "3") (pinfunction "DP_3") (pintype "passive"))
      (node (ref "U$3") (pin "3") (pinfunction "DP_3") (pintype "passive"))
      (node (ref "U$4") (pin "3") (pinfunction "DP_3") (pintype "passive"))
      (node (ref "U$5") (pin "3") (pinfunction "DP_3") (pintype "passive"))
    )
    (net (code "49") (name "SEG_DP_SOURCE") (class "Default")
      (node (ref "JP7") (pin "1") (pinfunction "1_1") (pintype "passive"))
      (node (ref "M11") (pin "3") (pinfunction "D_3") (pintype "passive"))
    )
    (net (code "50") (name "SEG_E") (class "Default")
      (node (ref "M8") (pin "3") (pinfunction "D_3") (pintype "passive"))
      (node (ref "U$1") (pin "1") (pinfunction "E_1") (pintype "passive"))
      (node (ref "U$2") (pin "1") (pinfunction "E_1") (pintype "passive"))
      (node (ref "U$3") (pin "1") (pinfunction "E_1") (pintype "passive"))
      (node (ref "U$4") (pin "1") (pinfunction "E_1") (pintype "passive"))
      (node (ref "U$5") (pin "1") (pinfunction "E_1") (pintype "passive"))
    )
    (net (code "51") (name "SEG_F") (class "Default")
      (node (ref "M9") (pin "3") (pinfunction "D_3") (pintype "passive"))
      (node (ref "U$1") (pin "10") (pinfunction "F_10") (pintype "passive"))
      (node (ref "U$2") (pin "10") (pinfunction "F_10") (pintype "passive"))
      (node (ref "U$3") (pin "10") (pinfunction "F_10") (pintype "passive"))
      (node (ref "U$4") (pin "10") (pinfunction "F_10") (pintype "passive"))
      (node (ref "U$5") (pin "10") (pinfunction "F_10") (pintype "passive"))
    )
    (net (code "52") (name "SEG_G") (class "Default")
      (node (ref "M10") (pin "3") (pinfunction "D_3") (pintype "passive"))
      (node (ref "U$1") (pin "5") (pinfunction "G_5") (pintype "passive"))
      (node (ref "U$2") (pin "5") (pinfunction "G_5") (pintype "passive"))
      (node (ref "U$3") (pin "5") (pinfunction "G_5") (pintype "passive"))
      (node (ref "U$4") (pin "5") (pinfunction "G_5") (pintype "passive"))
      (node (ref "U$5") (pin "5") (pinfunction "G_5") (pintype "passive"))
    )
    (net (code "53") (name "unconnected-(U$1-P$1-Pad6)") (class "Default")
      (node (ref "U$1") (pin "6") (pinfunction "P$1_6") (pintype "passive"))
    )
    (net (code "54") (name "unconnected-(U$2-P$1-Pad6)") (class "Default")
      (node (ref "U$2") (pin "6") (pinfunction "P$1_6") (pintype "passive"))
    )
    (net (code "55") (name "unconnected-(U$3-P$1-Pad6)") (class "Default")
      (node (ref "U$3") (pin "6") (pinfunction "P$1_6") (pintype "passive"))
    )
    (net (code "56") (name "unconnected-(U$4-P$1-Pad6)") (class "Default")
      (node (ref "U$4") (pin "6") (pinfunction "P$1_6") (pintype "passive"))
    )
    (net (code "57") (name "unconnected-(U$5-P$1-Pad6)") (class "Default")
      (node (ref "U$5") (pin "6") (pinfunction "P$1_6") (pintype "passive"))
    )
  )
)
